# ADC.net
KiCad netlist of a schematic drawn in Altium Designer
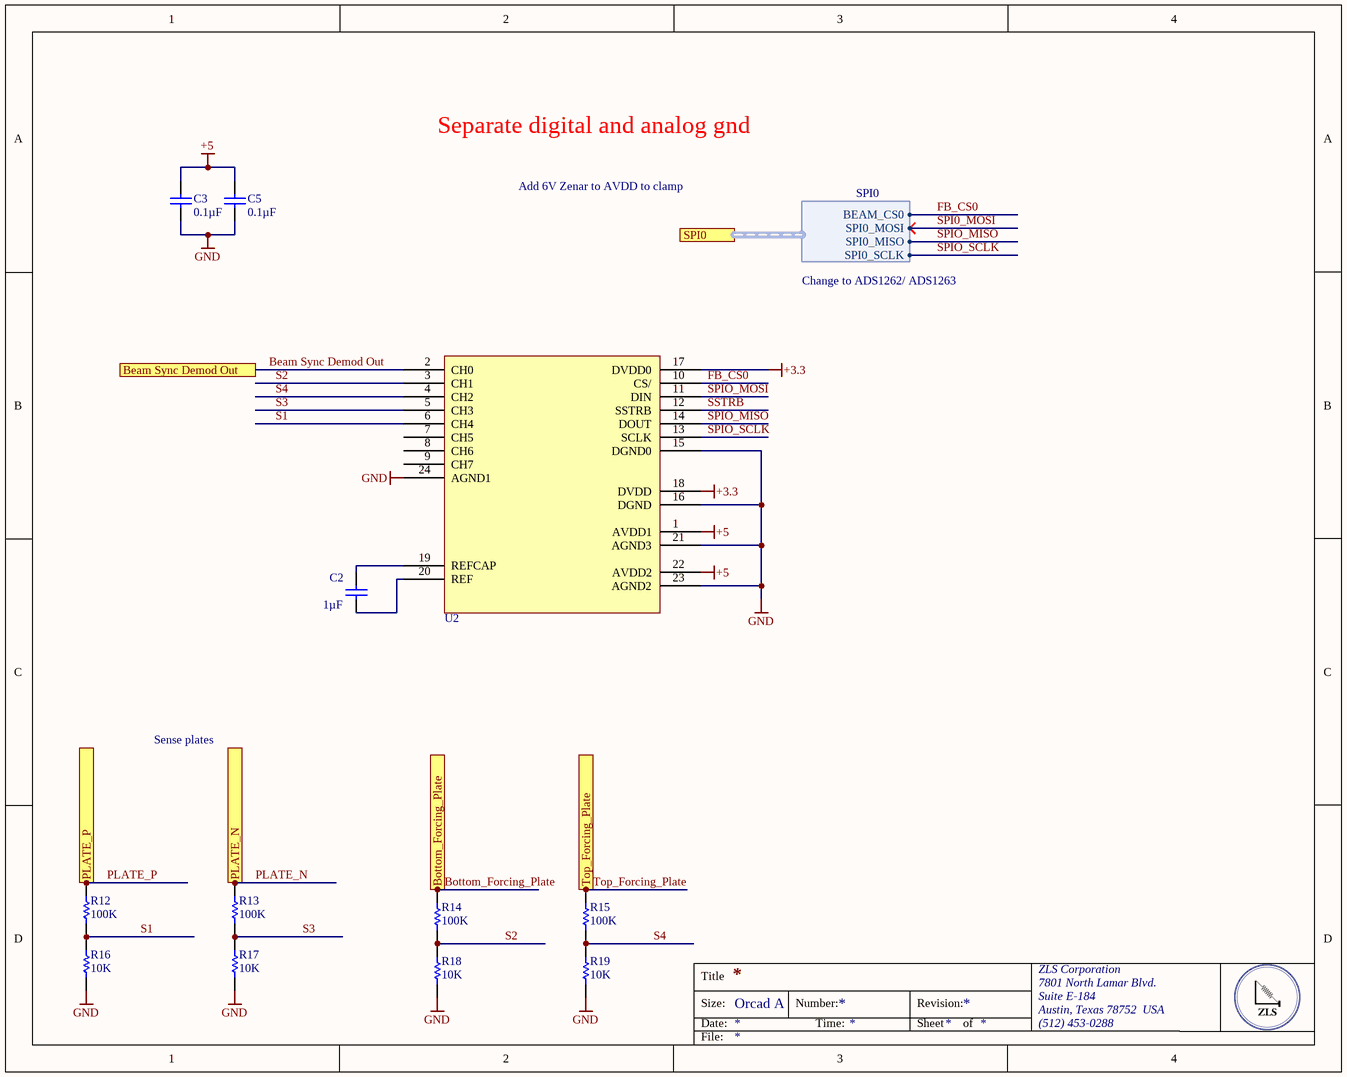
[diagram p0: ADC.SchDoc]

(export (version "E")
  (design (tool "Eeschema 10.0.6"))
  (components
    (comp (ref "C2")
      (value "CAP CER 0.1UF 25V X7R 0805")
      (footprint "CAPC0805(2012)145_N")
      (fields
        (field (name "MANUFACTURER") "Murata Electronics North America")
        (field (name "MANUFACTURER PART NUMBER") "GRM21BR71E104KA01L")
        (field (name "CAPACITANCE") "1µF")
        (field (name "TOLERANCE") "±10%")
      )
      (libsource (lib "Altium Content Vault") (part "CMP-1036-04795-1"))
    )
    (comp (ref "C3")
      (value "CAP CER 0.1UF 25V X7R 0805")
      (footprint "CAPC0805(2012)145_N")
      (fields
        (field (name "MANUFACTURER") "Murata Electronics North America")
        (field (name "MANUFACTURER PART NUMBER") "GRM21BR71E104KA01L")
        (field (name "CAPACITANCE") "0.1µF")
        (field (name "TOLERANCE") "±10%")
      )
      (libsource (lib "Altium Content Vault") (part "CMP-1036-04795-1"))
    )
    (comp (ref "C5")
      (value "CAP CER 0.1UF 25V X7R 0805")
      (footprint "CAPC0805(2012)145_N")
      (fields
        (field (name "MANUFACTURER") "Murata Electronics North America")
        (field (name "MANUFACTURER PART NUMBER") "GRM21BR71E104KA01L")
        (field (name "CAPACITANCE") "0.1µF")
        (field (name "TOLERANCE") "±10%")
      )
      (libsource (lib "Altium Content Vault") (part "CMP-1036-04795-1"))
    )
    (comp (ref "R12")
      (value "100K")
      (footprint "RESC0402(1005)_M")
      (libsource (lib "Altium Content Vault") (part "CMP-1011-00463-1"))
    )
    (comp (ref "R13")
      (value "100K")
      (footprint "RESC0402(1005)_M")
      (libsource (lib "Altium Content Vault") (part "CMP-1011-00463-1"))
    )
    (comp (ref "R14")
      (value "100K")
      (footprint "RESC0402(1005)_M")
      (libsource (lib "Altium Content Vault") (part "CMP-1011-00463-1"))
    )
    (comp (ref "R15")
      (value "100K")
      (footprint "RESC0402(1005)_M")
      (libsource (lib "Altium Content Vault") (part "CMP-1011-00463-1"))
    )
    (comp (ref "R16")
      (value "10K")
      (footprint "RESC0402(1005)_M")
      (libsource (lib "Altium Content Vault") (part "CMP-1011-00463-1"))
    )
    (comp (ref "R17")
      (value "10K")
      (footprint "RESC0402(1005)_M")
      (libsource (lib "Altium Content Vault") (part "CMP-1011-00463-1"))
    )
    (comp (ref "R18")
      (value "10K")
      (footprint "RESC0402(1005)_M")
      (libsource (lib "Altium Content Vault") (part "CMP-1011-00463-1"))
    )
    (comp (ref "R19")
      (value "10K")
      (footprint "RESC0402(1005)_M")
      (libsource (lib "Altium Content Vault") (part "CMP-1011-00463-1"))
    )
    (comp (ref "U2")
      (value "MAX1300")
      (footprint "MAX1300")
      (libsource (lib "ZLS_Schematic_lib") (part "MAX1300"))
    )
  )
  (nets
    (net (code "2") (name "+3.3") (class "Default")
      (node (ref "U2") (pin "17") (pinfunction "DVDD0_17") (pintype "passive"))
      (node (ref "U2") (pin "18") (pinfunction "DVDD_18") (pintype "passive"))
    )
    (net (code "3") (name "+5") (class "Default")
      (node (ref "C3") (pin "2") (pinfunction "2_2") (pintype "passive"))
      (node (ref "C5") (pin "2") (pinfunction "2_2") (pintype "passive"))
      (node (ref "U2") (pin "1") (pinfunction "AVDD1_1") (pintype "passive"))
      (node (ref "U2") (pin "22") (pinfunction "AVDD2_22") (pintype "passive"))
    )
    (net (code "4") (name "/Beam Sync Demod Out") (class "Default")
      (node (ref "U2") (pin "2") (pinfunction "CH0_2") (pintype "passive"))
    )
    (net (code "5") (name "/Bottom_Forcing_Plate") (class "Default")
      (node (ref "R14") (pin "2") (pinfunction "2_2") (pintype "passive"))
    )
    (net (code "6") (name "/FB_CS0") (class "Default")
      (node (ref "U2") (pin "10") (pinfunction "CS/_10") (pintype "passive"))
    )
    (net (code "7") (name "/PLATE_N") (class "Default")
      (node (ref "R13") (pin "2") (pinfunction "2_2") (pintype "passive"))
    )
    (net (code "8") (name "/PLATE_P") (class "Default")
      (node (ref "R12") (pin "2") (pinfunction "2_2") (pintype "passive"))
    )
    (net (code "9") (name "/S1") (class "Default")
      (node (ref "R12") (pin "1") (pinfunction "1_1") (pintype "passive"))
      (node (ref "R16") (pin "2") (pinfunction "2_2") (pintype "passive"))
      (node (ref "U2") (pin "6") (pinfunction "CH4_6") (pintype "passive"))
    )
    (net (code "10") (name "/S2") (class "Default")
      (node (ref "R14") (pin "1") (pinfunction "1_1") (pintype "passive"))
      (node (ref "R18") (pin "2") (pinfunction "2_2") (pintype "passive"))
      (node (ref "U2") (pin "3") (pinfunction "CH1_3") (pintype "passive"))
    )
    (net (code "11") (name "/S3") (class "Default")
      (node (ref "R13") (pin "1") (pinfunction "1_1") (pintype "passive"))
      (node (ref "R17") (pin "2") (pinfunction "2_2") (pintype "passive"))
      (node (ref "U2") (pin "5") (pinfunction "CH3_5") (pintype "passive"))
    )
    (net (code "12") (name "/S4") (class "Default")
      (node (ref "R15") (pin "1") (pinfunction "1_1") (pintype "passive"))
      (node (ref "R19") (pin "2") (pinfunction "2_2") (pintype "passive"))
      (node (ref "U2") (pin "4") (pinfunction "CH2_4") (pintype "passive"))
    )
    (net (code "14") (name "/SPIO_MISO") (class "Default")
      (node (ref "U2") (pin "14") (pinfunction "DOUT_14") (pintype "passive"))
    )
    (net (code "15") (name "/SPIO_MOSI") (class "Default")
      (node (ref "U2") (pin "11") (pinfunction "DIN_11") (pintype "passive"))
    )
    (net (code "16") (name "/SPIO_SCLK") (class "Default")
      (node (ref "U2") (pin "13") (pinfunction "SCLK_13") (pintype "passive"))
    )
    (net (code "17") (name "/SSTRB") (class "Default")
      (node (ref "U2") (pin "12") (pinfunction "SSTRB_12") (pintype "passive"))
    )
    (net (code "18") (name "/Top_Forcing_Plate") (class "Default")
      (node (ref "R15") (pin "2") (pinfunction "2_2") (pintype "passive"))
    )
    (net (code "20") (name "GND") (class "Default")
      (node (ref "C3") (pin "1") (pinfunction "1_1") (pintype "passive"))
      (node (ref "C5") (pin "1") (pinfunction "1_1") (pintype "passive"))
      (node (ref "R16") (pin "1") (pinfunction "1_1") (pintype "passive"))
      (node (ref "R17") (pin "1") (pinfunction "1_1") (pintype "passive"))
      (node (ref "R18") (pin "1") (pinfunction "1_1") (pintype "passive"))
      (node (ref "R19") (pin "1") (pinfunction "1_1") (pintype "passive"))
      (node (ref "U2") (pin "15") (pinfunction "DGND0_15") (pintype "passive"))
      (node (ref "U2") (pin "16") (pinfunction "DGND_16") (pintype "passive"))
      (node (ref "U2") (pin "21") (pinfunction "AGND3_21") (pintype "passive"))
      (node (ref "U2") (pin "23") (pinfunction "AGND2_23") (pintype "passive"))
      (node (ref "U2") (pin "24") (pinfunction "AGND1_24") (pintype "passive"))
    )
    (net (code "21") (name "Net-(U2-REF)") (class "Default")
      (node (ref "C2") (pin "2") (pinfunction "2_2") (pintype "passive"))
      (node (ref "U2") (pin "20") (pinfunction "REF_20") (pintype "passive"))
    )
    (net (code "22") (name "Net-(U2-REFCAP)") (class "Default")
      (node (ref "C2") (pin "1") (pinfunction "1_1") (pintype "passive"))
      (node (ref "U2") (pin "19") (pinfunction "REFCAP_19") (pintype "passive"))
    )
    (net (code "23") (name "unconnected-(U2-CH5-Pad7)") (class "Default")
      (node (ref "U2") (pin "7") (pinfunction "CH5_7") (pintype "passive"))
    )
    (net (code "24") (name "unconnected-(U2-CH6-Pad8)") (class "Default")
      (node (ref "U2") (pin "8") (pinfunction "CH6_8") (pintype "passive"))
    )
    (net (code "25") (name "unconnected-(U2-CH7-Pad9)") (class "Default")
      (node (ref "U2") (pin "9") (pinfunction "CH7_9") (pintype "passive"))
    )
  )
)
